# midispoof.net
KiCad netlist of a schematic drawn in EAGLE
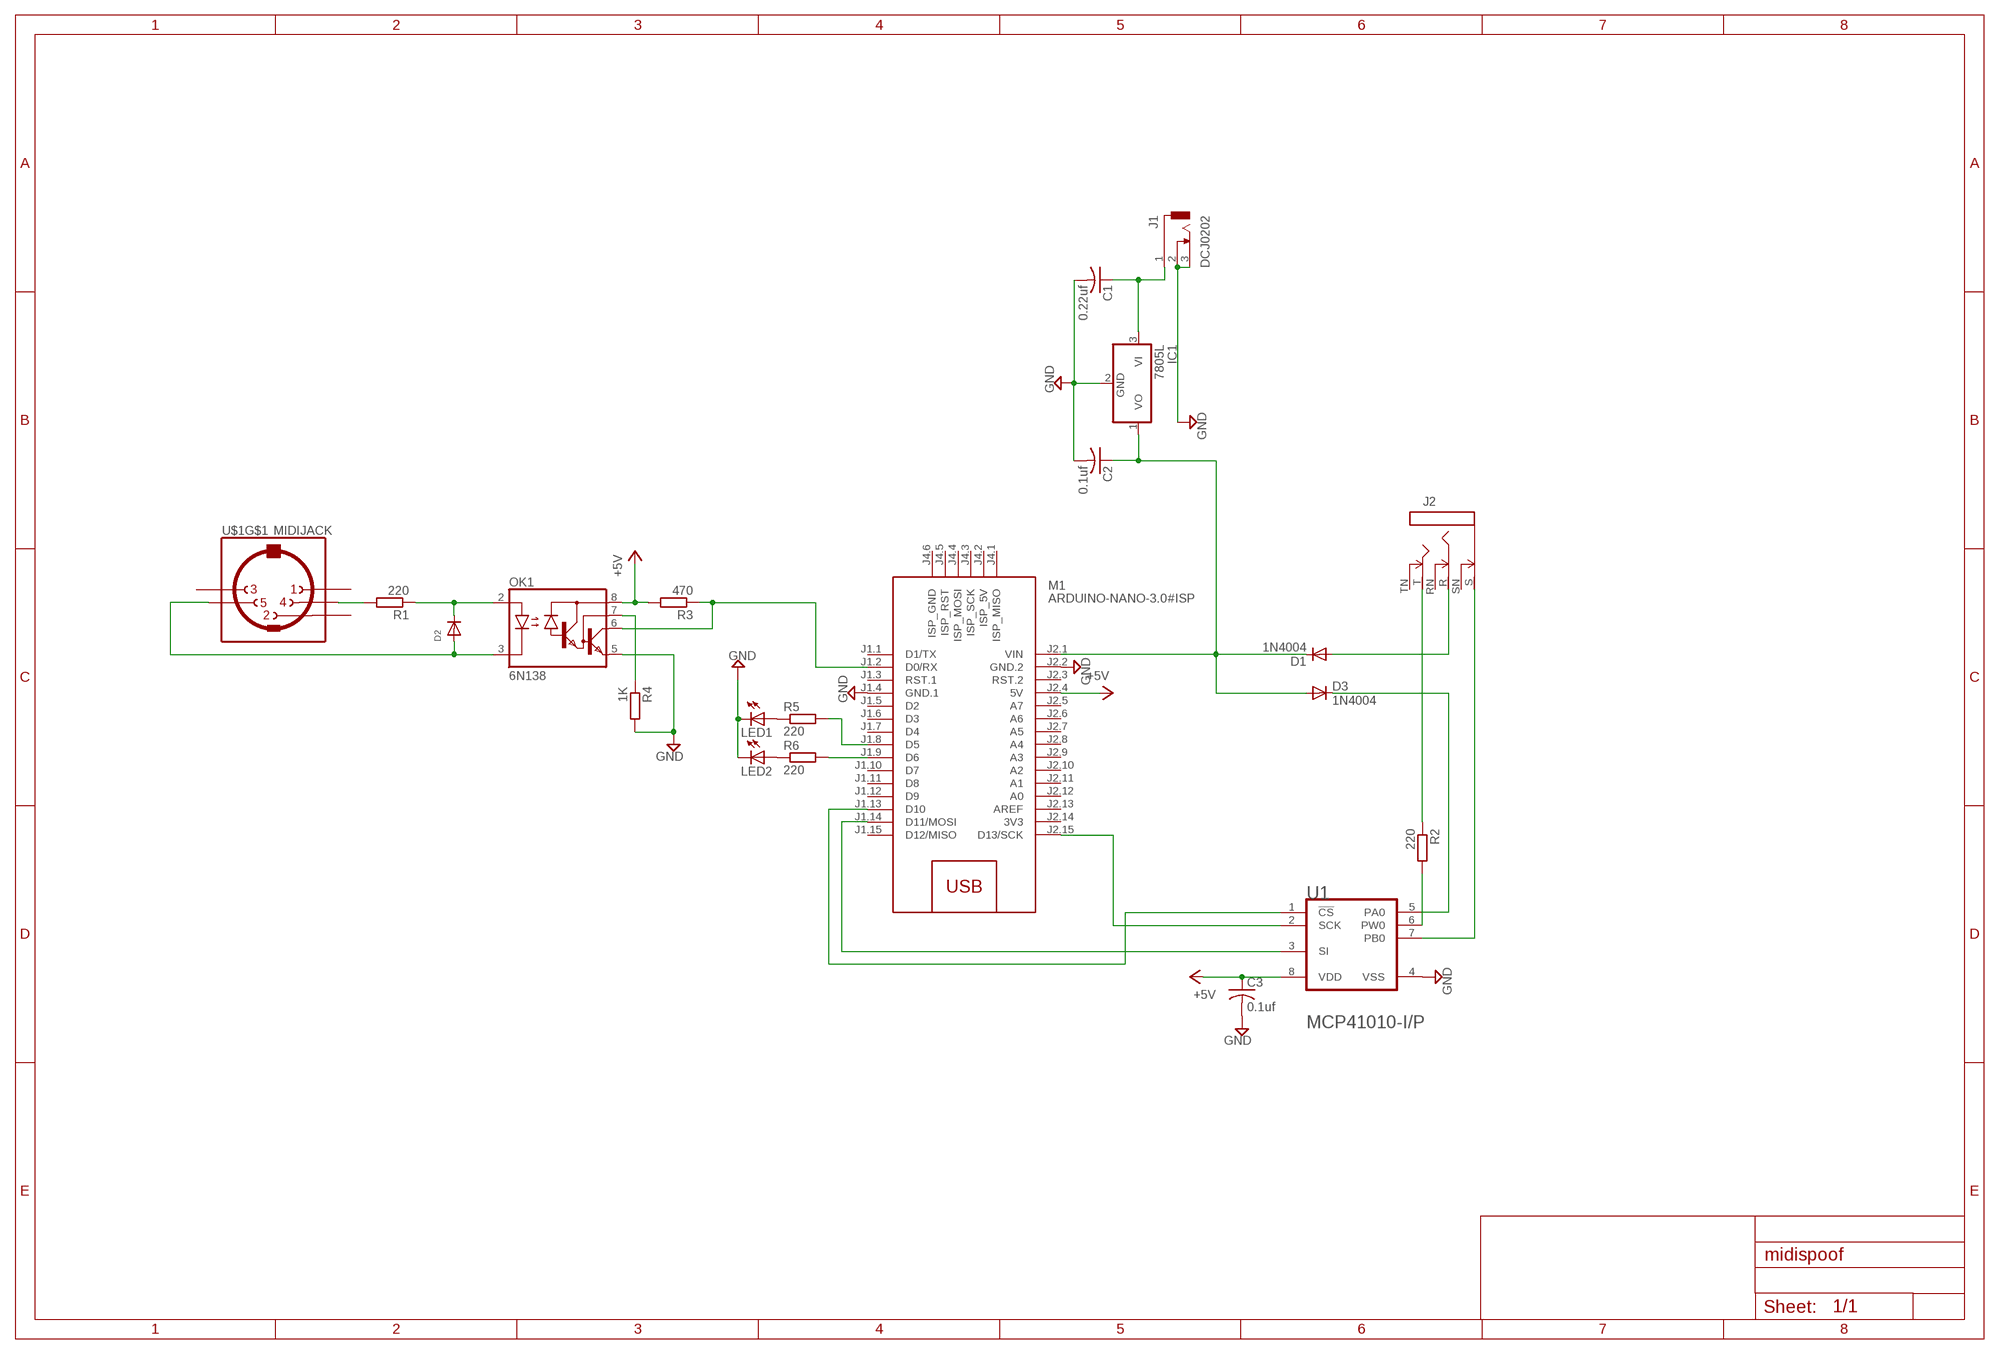
[diagram p0: schematic, sheet 1]

(export (version "E")
  (design (tool "Eeschema 10.0.6"))
  (components
    (comp (ref "C1")
      (value "0.22uf")
      (footprint "eagle-import:C050-025X075")
      (libsource (lib "eagle-import") (part "C-US050-025X075"))
    )
    (comp (ref "C2")
      (value "0.1uf")
      (footprint "eagle-import:C050-025X075")
      (libsource (lib "eagle-import") (part "C-US050-025X075"))
    )
    (comp (ref "C3")
      (value "0.1uf")
      (footprint "eagle-import:C050-025X075")
      (libsource (lib "eagle-import") (part "C-US050-025X075"))
    )
    (comp (ref "D1")
      (value "1N4004")
      (footprint "eagle-import:DO41-10")
      (libsource (lib "eagle-import") (part "1N4004"))
    )
    (comp (ref "D2")
      (value "DIODEDO-1N4148")
      (footprint "eagle-import:DO-1N4148")
      (libsource (lib "eagle-import") (part "DIODEDO-1N4148"))
    )
    (comp (ref "D3")
      (value "1N4004")
      (footprint "eagle-import:DO41-10")
      (libsource (lib "eagle-import") (part "1N4004"))
    )
    (comp (ref "IC1")
      (value "7805L")
      (footprint "eagle-import:TO92")
      (libsource (lib "eagle-import") (part "78L05"))
    )
    (comp (ref "J1")
      (value "DCJ0202")
      (footprint "eagle-import:DCJ0202")
      (libsource (lib "eagle-import") (part "DCJ0202"))
    )
    (comp (ref "J2")
      (value "STEREOSWS")
      (footprint "eagle-import:NMJ6HC-S")
      (libsource (lib "eagle-import") (part "STEREOSWS"))
    )
    (comp (ref "LED1")
      (value "LED3MM")
      (footprint "eagle-import:LED3MM")
      (libsource (lib "eagle-import") (part "LED3MM"))
    )
    (comp (ref "LED2")
      (value "LED3MM")
      (footprint "eagle-import:LED3MM")
      (libsource (lib "eagle-import") (part "LED3MM"))
    )
    (comp (ref "M1")
      (value "ARDUINO-NANO-3.0#ISP")
      (footprint "eagle-import:ARDUINO-NANO-3.0#ISP")
      (libsource (lib "eagle-import") (part "ARDUINO-NANO-3.0#ISP"))
    )
    (comp (ref "OK1")
      (value "6N138")
      (footprint "eagle-import:DIL08")
      (fields (field (name "MF") "VISHAY/TELEFUNKEN"))
      (libsource (lib "eagle-import") (part "6N138"))
    )
    (comp (ref "R1")
      (value "220")
      (footprint "eagle-import:0207_10")
      (libsource (lib "eagle-import") (part "R-EU_0207/10"))
    )
    (comp (ref "R2")
      (value "220")
      (footprint "eagle-import:0207_10")
      (libsource (lib "eagle-import") (part "R-EU_0207/10"))
    )
    (comp (ref "R3")
      (value "470")
      (footprint "eagle-import:0207_10")
      (libsource (lib "eagle-import") (part "R-EU_0207/10"))
    )
    (comp (ref "R4")
      (value "1K")
      (footprint "eagle-import:0207_10")
      (libsource (lib "eagle-import") (part "R-EU_0207/10"))
    )
    (comp (ref "R5")
      (value "220")
      (footprint "eagle-import:0207_10")
      (libsource (lib "eagle-import") (part "R-EU_0207/10"))
    )
    (comp (ref "R6")
      (value "220")
      (footprint "eagle-import:0207_10")
      (libsource (lib "eagle-import") (part "R-EU_0207/10"))
    )
    (comp (ref "U$1")
      (value "MIDIJACK")
      (footprint "eagle-import:CP-2350")
      (libsource (lib "eagle-import") (part "MIDIJACK"))
    )
    (comp (ref "U1")
      (value "MICROCHIP_MCP41010-I-PMICROCHIP_MCP41010-I-P_0_0")
      (footprint "eagle-import:MICROCHIP_MCP41010-I-P_0")
      (fields (field (name "MF") "Microchip") (field (name "MPN") "MCP41010-I/P"))
      (libsource (lib "eagle-import") (part "MICROCHIP_MCP41010-I-PMICROCHIP_MCP41010-I-P_0_0"))
    )
  )
  (nets
    (net (code "1") (name "+5V") (class "Default")
      (node (ref "C3") (pin "1") (pinfunction "1_1") (pintype "passive"))
      (node (ref "M1") (pin "J2.4") (pinfunction "5V_J2.4") (pintype "power_in"))
      (node (ref "OK1") (pin "8") (pinfunction "VCC_8") (pintype "passive"))
      (node (ref "R3") (pin "2") (pinfunction "2_2") (pintype "passive"))
      (node (ref "U1") (pin "8") (pinfunction "VDD_8") (pintype "power_in"))
    )
    (net (code "2") (name "/3V3") (class "Default")
      (node (ref "M1") (pin "J2.14") (pinfunction "3V3_J2.14") (pintype "power_in"))
    )
    (net (code "3") (name "GND") (class "Default")
      (node (ref "C1") (pin "2") (pinfunction "2_2") (pintype "passive"))
      (node (ref "C2") (pin "2") (pinfunction "2_2") (pintype "passive"))
      (node (ref "C3") (pin "2") (pinfunction "2_2") (pintype "passive"))
      (node (ref "IC1") (pin "2") (pinfunction "GND_2") (pintype "passive"))
      (node (ref "J1") (pin "2") (pinfunction "2_2") (pintype "passive"))
      (node (ref "J1") (pin "3") (pinfunction "3_3") (pintype "passive"))
      (node (ref "LED1") (pin "K") (pinfunction "C_K") (pintype "passive"))
      (node (ref "LED2") (pin "K") (pinfunction "C_K") (pintype "passive"))
      (node (ref "M1") (pin "J1.4") (pinfunction "GND.1_J1.4") (pintype "power_in"))
      (node (ref "M1") (pin "J2.2") (pinfunction "GND.2_J2.2") (pintype "power_in"))
      (node (ref "OK1") (pin "5") (pinfunction "GND_5") (pintype "passive"))
      (node (ref "R4") (pin "2") (pinfunction "2_2") (pintype "passive"))
      (node (ref "U1") (pin "4") (pinfunction "VSS_4") (pintype "power_in"))
    )
    (net (code "4") (name "Net-(D1-PadA)") (class "Default")
      (node (ref "D1") (pin "A") (pinfunction "A_A") (pintype "passive"))
      (node (ref "J2") (pin "R") (pinfunction "R_R") (pintype "passive"))
    )
    (net (code "5") (name "Net-(IC1-VI)") (class "Default")
      (node (ref "C1") (pin "1") (pinfunction "1_1") (pintype "passive"))
      (node (ref "IC1") (pin "3") (pinfunction "VI_3") (pintype "input"))
      (node (ref "J1") (pin "1") (pinfunction "1_1") (pintype "passive"))
    )
    (net (code "6") (name "Net-(IC1-VO)") (class "Default")
      (node (ref "C2") (pin "1") (pinfunction "1_1") (pintype "passive"))
      (node (ref "D1") (pin "C") (pinfunction "C_C") (pintype "passive"))
      (node (ref "D3") (pin "A") (pinfunction "A_A") (pintype "passive"))
      (node (ref "IC1") (pin "1") (pinfunction "VO_1") (pintype "passive"))
      (node (ref "M1") (pin "J2.1") (pinfunction "VIN_J2.1") (pintype "power_in"))
    )
    (net (code "7") (name "Net-(J2-PadT)") (class "Default")
      (node (ref "J2") (pin "T") (pinfunction "T_T") (pintype "passive"))
      (node (ref "R2") (pin "1") (pinfunction "1_1") (pintype "passive"))
    )
    (net (code "8") (name "Net-(LED1-PadA)") (class "Default")
      (node (ref "LED1") (pin "A") (pinfunction "A_A") (pintype "passive"))
      (node (ref "R5") (pin "1") (pinfunction "1_1") (pintype "passive"))
    )
    (net (code "9") (name "Net-(LED2-PadA)") (class "Default")
      (node (ref "LED2") (pin "A") (pinfunction "A_A") (pintype "passive"))
      (node (ref "R6") (pin "1") (pinfunction "1_1") (pintype "passive"))
    )
    (net (code "10") (name "Net-(M1-D0{slash}RX)") (class "Default")
      (node (ref "M1") (pin "J1.2") (pinfunction "D0/RX_J1.2") (pintype "bidirectional"))
      (node (ref "OK1") (pin "6") (pinfunction "VO_6") (pintype "passive"))
      (node (ref "R3") (pin "1") (pinfunction "1_1") (pintype "passive"))
    )
    (net (code "11") (name "Net-(M1-D5)") (class "Default")
      (node (ref "M1") (pin "J1.8") (pinfunction "D5_J1.8") (pintype "bidirectional"))
      (node (ref "R5") (pin "2") (pinfunction "2_2") (pintype "passive"))
    )
    (net (code "12") (name "Net-(M1-D6)") (class "Default")
      (node (ref "M1") (pin "J1.9") (pinfunction "D6_J1.9") (pintype "bidirectional"))
      (node (ref "R6") (pin "2") (pinfunction "2_2") (pintype "passive"))
    )
    (net (code "13") (name "Net-(M1-D10)") (class "Default")
      (node (ref "M1") (pin "J1.13") (pinfunction "D10_J1.13") (pintype "bidirectional"))
      (node (ref "U1") (pin "1") (pinfunction "~{CS}_1") (pintype "input"))
    )
    (net (code "14") (name "Net-(M1-D11{slash}MOSI)") (class "Default")
      (node (ref "M1") (pin "J1.14") (pinfunction "D11/MOSI_J1.14") (pintype "bidirectional"))
      (node (ref "U1") (pin "3") (pinfunction "SI_3") (pintype "input"))
    )
    (net (code "15") (name "Net-(M1-D13{slash}SCK)") (class "Default")
      (node (ref "M1") (pin "J2.15") (pinfunction "D13/SCK_J2.15") (pintype "bidirectional"))
      (node (ref "U1") (pin "2") (pinfunction "SCK_2") (pintype "input"))
    )
    (net (code "16") (name "Net-(OK1-A)") (class "Default")
      (node (ref "D2") (pin "C") (pinfunction "C_C") (pintype "passive"))
      (node (ref "OK1") (pin "2") (pinfunction "A_2") (pintype "passive"))
      (node (ref "R1") (pin "1") (pinfunction "1_1") (pintype "passive"))
    )
    (net (code "17") (name "Net-(OK1-C)") (class "Default")
      (node (ref "D2") (pin "A") (pinfunction "A_A") (pintype "passive"))
      (node (ref "OK1") (pin "3") (pinfunction "C_3") (pintype "passive"))
      (node (ref "U$1") (pin "5") (pinfunction "5_5") (pintype "passive"))
    )
    (net (code "18") (name "Net-(OK1-VB)") (class "Default")
      (node (ref "OK1") (pin "7") (pinfunction "VB_7") (pintype "passive"))
      (node (ref "R4") (pin "1") (pinfunction "1_1") (pintype "passive"))
    )
    (net (code "19") (name "Net-(R1-Pad2)") (class "Default")
      (node (ref "R1") (pin "2") (pinfunction "2_2") (pintype "passive"))
      (node (ref "U$1") (pin "4") (pinfunction "4_4") (pintype "passive"))
    )
    (net (code "20") (name "Net-(U1-PA0)") (class "Default")
      (node (ref "D3") (pin "C") (pinfunction "C_C") (pintype "passive"))
      (node (ref "U1") (pin "5") (pinfunction "PA0_5") (pintype "passive"))
    )
    (net (code "21") (name "Net-(U1-PB0)") (class "Default")
      (node (ref "J2") (pin "S") (pinfunction "S_S") (pintype "passive"))
      (node (ref "U1") (pin "7") (pinfunction "PB0_7") (pintype "passive"))
    )
    (net (code "22") (name "Net-(U1-PW0)") (class "Default")
      (node (ref "R2") (pin "2") (pinfunction "2_2") (pintype "passive"))
      (node (ref "U1") (pin "6") (pinfunction "PW0_6") (pintype "passive"))
    )
    (net (code "23") (name "unconnected-(J2-PadRN)") (class "Default")
      (node (ref "J2") (pin "RN") (pinfunction "RN_RN") (pintype "passive"))
    )
    (net (code "24") (name "unconnected-(J2-PadSN)") (class "Default")
      (node (ref "J2") (pin "SN") (pinfunction "SN_SN") (pintype "passive"))
    )
    (net (code "25") (name "unconnected-(J2-PadTN)") (class "Default")
      (node (ref "J2") (pin "TN") (pinfunction "TN_TN") (pintype "passive"))
    )
    (net (code "26") (name "unconnected-(M1-A0-PadJ2.12)") (class "Default")
      (node (ref "M1") (pin "J2.12") (pinfunction "A0_J2.12") (pintype "bidirectional"))
    )
    (net (code "27") (name "unconnected-(M1-A1-PadJ2.11)") (class "Default")
      (node (ref "M1") (pin "J2.11") (pinfunction "A1_J2.11") (pintype "bidirectional"))
    )
    (net (code "28") (name "unconnected-(M1-A2-PadJ2.10)") (class "Default")
      (node (ref "M1") (pin "J2.10") (pinfunction "A2_J2.10") (pintype "bidirectional"))
    )
    (net (code "29") (name "unconnected-(M1-A3-PadJ2.9)") (class "Default")
      (node (ref "M1") (pin "J2.9") (pinfunction "A3_J2.9") (pintype "bidirectional"))
    )
    (net (code "30") (name "unconnected-(M1-A4-PadJ2.8)") (class "Default")
      (node (ref "M1") (pin "J2.8") (pinfunction "A4_J2.8") (pintype "bidirectional"))
    )
    (net (code "31") (name "unconnected-(M1-A5-PadJ2.7)") (class "Default")
      (node (ref "M1") (pin "J2.7") (pinfunction "A5_J2.7") (pintype "bidirectional"))
    )
    (net (code "32") (name "unconnected-(M1-A6-PadJ2.6)") (class "Default")
      (node (ref "M1") (pin "J2.6") (pinfunction "A6_J2.6") (pintype "bidirectional"))
    )
    (net (code "33") (name "unconnected-(M1-A7-PadJ2.5)") (class "Default")
      (node (ref "M1") (pin "J2.5") (pinfunction "A7_J2.5") (pintype "bidirectional"))
    )
    (net (code "34") (name "unconnected-(M1-AREF-PadJ2.13)") (class "Default")
      (node (ref "M1") (pin "J2.13") (pinfunction "AREF_J2.13") (pintype "bidirectional"))
    )
    (net (code "35") (name "unconnected-(M1-D1{slash}TX-PadJ1.1)") (class "Default")
      (node (ref "M1") (pin "J1.1") (pinfunction "D1/TX_J1.1") (pintype "bidirectional"))
    )
    (net (code "36") (name "unconnected-(M1-D2-PadJ1.5)") (class "Default")
      (node (ref "M1") (pin "J1.5") (pinfunction "D2_J1.5") (pintype "bidirectional"))
    )
    (net (code "37") (name "unconnected-(M1-D3-PadJ1.6)") (class "Default")
      (node (ref "M1") (pin "J1.6") (pinfunction "D3_J1.6") (pintype "bidirectional"))
    )
    (net (code "38") (name "unconnected-(M1-D4-PadJ1.7)") (class "Default")
      (node (ref "M1") (pin "J1.7") (pinfunction "D4_J1.7") (pintype "bidirectional"))
    )
    (net (code "39") (name "unconnected-(M1-D7-PadJ1.10)") (class "Default")
      (node (ref "M1") (pin "J1.10") (pinfunction "D7_J1.10") (pintype "bidirectional"))
    )
    (net (code "40") (name "unconnected-(M1-D8-PadJ1.11)") (class "Default")
      (node (ref "M1") (pin "J1.11") (pinfunction "D8_J1.11") (pintype "bidirectional"))
    )
    (net (code "41") (name "unconnected-(M1-D9-PadJ1.12)") (class "Default")
      (node (ref "M1") (pin "J1.12") (pinfunction "D9_J1.12") (pintype "bidirectional"))
    )
    (net (code "42") (name "unconnected-(M1-D12{slash}MISO-PadJ1.15)") (class "Default")
      (node (ref "M1") (pin "J1.15") (pinfunction "D12/MISO_J1.15") (pintype "bidirectional"))
    )
    (net (code "43") (name "unconnected-(M1-ISP_5V-PadJ4.2)") (class "Default")
      (node (ref "M1") (pin "J4.2") (pinfunction "ISP_5V_J4.2") (pintype "bidirectional"))
    )
    (net (code "44") (name "unconnected-(M1-ISP_GND-PadJ4.6)") (class "Default")
      (node (ref "M1") (pin "J4.6") (pinfunction "ISP_GND_J4.6") (pintype "bidirectional"))
    )
    (net (code "45") (name "unconnected-(M1-ISP_MISO-PadJ4.1)") (class "Default")
      (node (ref "M1") (pin "J4.1") (pinfunction "ISP_MISO_J4.1") (pintype "bidirectional"))
    )
    (net (code "46") (name "unconnected-(M1-ISP_MOSI-PadJ4.4)") (class "Default")
      (node (ref "M1") (pin "J4.4") (pinfunction "ISP_MOSI_J4.4") (pintype "bidirectional"))
    )
    (net (code "47") (name "unconnected-(M1-ISP_RST-PadJ4.5)") (class "Default")
      (node (ref "M1") (pin "J4.5") (pinfunction "ISP_RST_J4.5") (pintype "bidirectional"))
    )
    (net (code "48") (name "unconnected-(M1-ISP_SCK-PadJ4.3)") (class "Default")
      (node (ref "M1") (pin "J4.3") (pinfunction "ISP_SCK_J4.3") (pintype "bidirectional"))
    )
    (net (code "49") (name "unconnected-(M1-RST.1-PadJ1.3)") (class "Default")
      (node (ref "M1") (pin "J1.3") (pinfunction "RST.1_J1.3") (pintype "bidirectional"))
    )
    (net (code "50") (name "unconnected-(M1-RST.2-PadJ2.3)") (class "Default")
      (node (ref "M1") (pin "J2.3") (pinfunction "RST.2_J2.3") (pintype "bidirectional"))
    )
    (net (code "51") (name "unconnected-(U$1-Pad1)") (class "Default")
      (node (ref "U$1") (pin "1") (pinfunction "1_1") (pintype "passive"))
    )
    (net (code "52") (name "unconnected-(U$1-Pad2)") (class "Default")
      (node (ref "U$1") (pin "2") (pinfunction "2_2") (pintype "passive"))
    )
    (net (code "53") (name "unconnected-(U$1-Pad3)") (class "Default")
      (node (ref "U$1") (pin "3") (pinfunction "3_3") (pintype "passive"))
    )
  )
)
